# Sheet4.net
KiCad netlist of a schematic drawn in Altium Designer
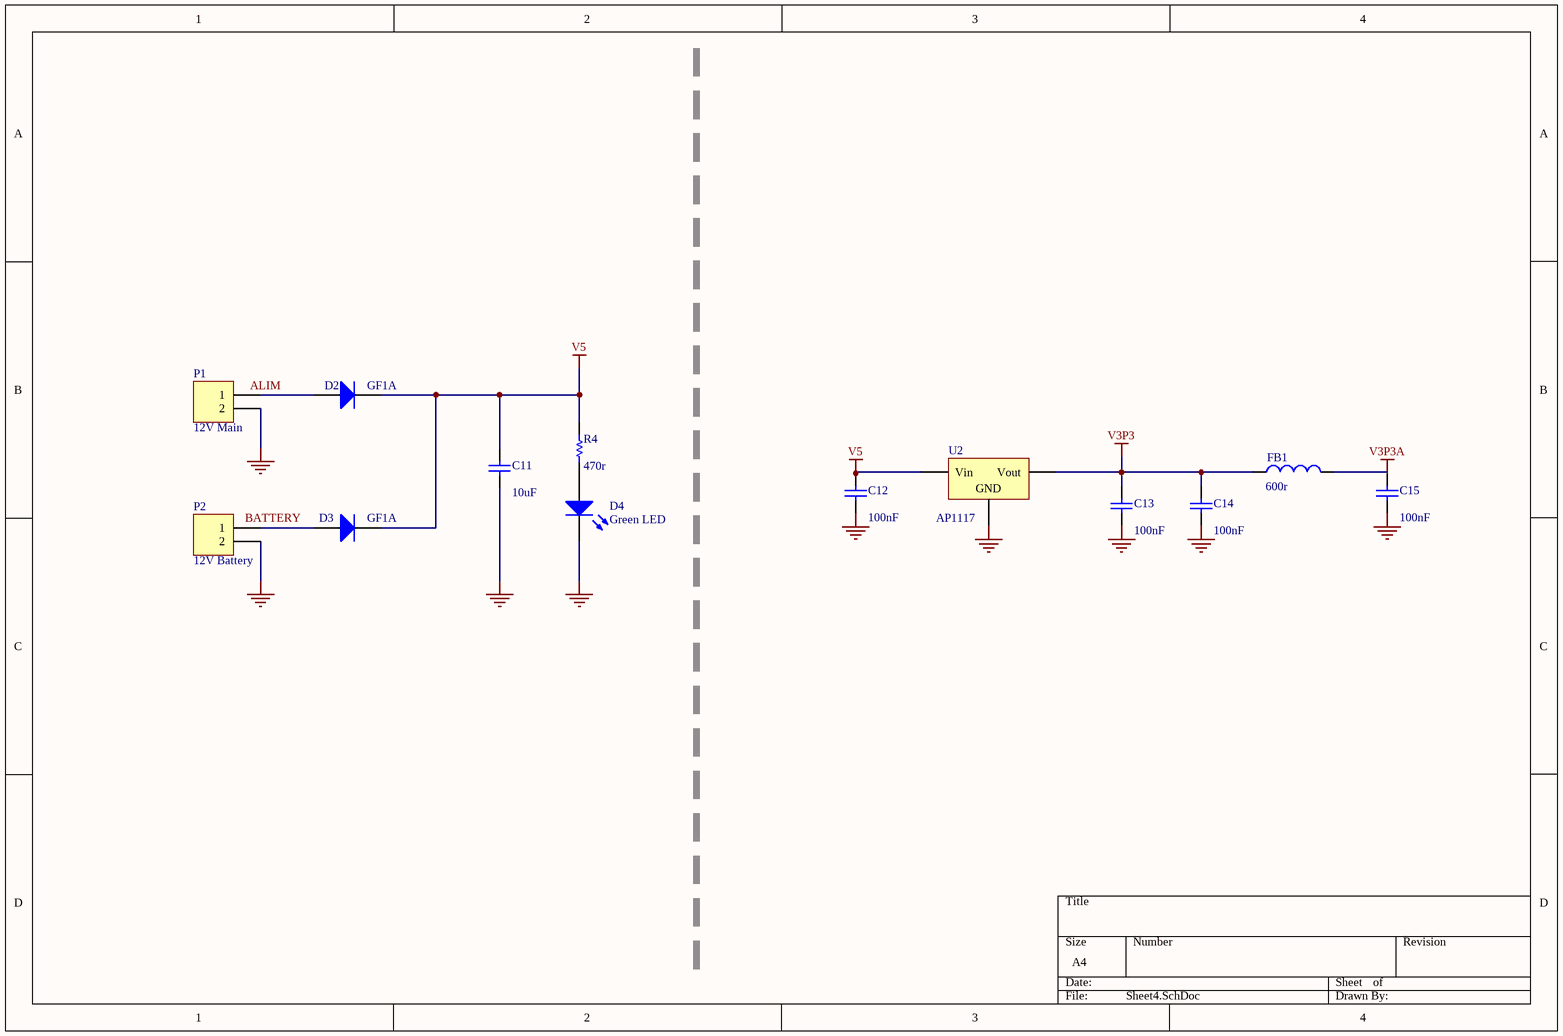
[diagram p0: Sheet4.SchDoc]

(export (version "E")
  (design (tool "Eeschema 10.0.6"))
  (components
    (comp (ref "C11")
      (value "10uF")
      (footprint "RAD-0.3")
      (description "Capacitor")
      (fields (field (name "Comment") "Cap") (field (name "PUBLISHER") "Altium Limited"))
      (libsource (lib "Miscellaneous Devices") (part "Cap"))
    )
    (comp (ref "C12")
      (value "100nF")
      (footprint "RAD-0.3")
      (description "Capacitor")
      (fields (field (name "Comment") "Cap") (field (name "PUBLISHER") "Altium Limited"))
      (libsource (lib "Miscellaneous Devices") (part "Cap"))
    )
    (comp (ref "C13")
      (value "100nF")
      (footprint "RAD-0.3")
      (description "Capacitor")
      (fields (field (name "Comment") "Cap") (field (name "PUBLISHER") "Altium Limited"))
      (libsource (lib "Miscellaneous Devices") (part "Cap"))
    )
    (comp (ref "C14")
      (value "100nF")
      (footprint "RAD-0.3")
      (description "Capacitor")
      (fields (field (name "Comment") "Cap") (field (name "PUBLISHER") "Altium Limited"))
      (libsource (lib "Miscellaneous Devices") (part "Cap"))
    )
    (comp (ref "C15")
      (value "100nF")
      (footprint "RAD-0.3")
      (description "Capacitor")
      (fields (field (name "Comment") "Cap") (field (name "PUBLISHER") "Altium Limited"))
      (libsource (lib "Miscellaneous Devices") (part "Cap"))
    )
    (comp (ref "D2")
      (value "GF1A")
      (footprint "SMC")
      (description "Default Diode")
      (fields (field (name "PUBLISHER") "Altium Limited"))
      (libsource (lib "Miscellaneous Devices") (part "Diode"))
    )
    (comp (ref "D3")
      (value "GF1A")
      (footprint "SMC")
      (description "Default Diode")
      (fields (field (name "PUBLISHER") "Altium Limited"))
      (libsource (lib "Miscellaneous Devices") (part "Diode"))
    )
    (comp (ref "D4")
      (value "Green LED")
      (footprint "3.2X1.6X1.1")
      (description "Typical RED, GREEN, YELLOW, AMBER GaAs LED")
      (fields (field (name "PUBLISHER") "Altium Limited"))
      (libsource (lib "Miscellaneous Devices") (part "LED2"))
    )
    (comp (ref "FB1")
      (value "600r")
      (footprint "0402-A")
      (description "Inductor")
      (fields (field (name "PUBLISHER") "Altium Limited"))
      (libsource (lib "Miscellaneous Devices") (part "Inductor"))
    )
    (comp (ref "P1")
      (value "12V Main")
      (footprint "HDR1X2")
      (description "Header, 2-Pin")
      (libsource (lib "Miscellaneous Connectors") (part "Header 2"))
    )
    (comp (ref "P2")
      (value "12V Battery")
      (footprint "HDR1X2")
      (description "Header, 2-Pin")
      (libsource (lib "Miscellaneous Connectors") (part "Header 2"))
    )
    (comp (ref "R4")
      (value "470r")
      (footprint "AXIAL-0.3")
      (description "Resistor")
      (fields (field (name "Comment") "Res1") (field (name "PUBLISHER") "Altium Limited"))
      (libsource (lib "Miscellaneous Devices") (part "Res1"))
    )
    (comp (ref "U2")
      (value "AP1117")
      (footprint "D2PAK_N")
      (description "Voltage Regulator")
      (fields (field (name "PUBLISHER") "Altium Limited"))
      (libsource (lib "Miscellaneous Devices") (part "Volt Reg"))
    )
  )
  (nets
    (net (code "3") (name "<NO NET>") (class "Default")
      (node (ref "C12") (pin "1") (pinfunction "1_1") (pintype "passive"))
      (node (ref "C13") (pin "1") (pinfunction "1_1") (pintype "passive"))
      (node (ref "C14") (pin "1") (pinfunction "1_1") (pintype "passive"))
      (node (ref "C15") (pin "1") (pinfunction "1_1") (pintype "passive"))
    )
    (net (code "4") (name "GND") (class "Default")
      (node (ref "C11") (pin "1") (pinfunction "1_1") (pintype "passive"))
      (node (ref "D4") (pin "2") (pinfunction "K_2") (pintype "passive"))
      (node (ref "P1") (pin "2") (pinfunction "2_2") (pintype "passive"))
      (node (ref "P2") (pin "2") (pinfunction "2_2") (pintype "passive"))
      (node (ref "U2") (pin "2") (pinfunction "GND_2") (pintype "passive"))
    )
    (net (code "5") (name "Net-(D2-A)") (class "Default")
      (node (ref "D2") (pin "1") (pinfunction "A_1") (pintype "passive"))
      (node (ref "P1") (pin "1") (pinfunction "1_1") (pintype "passive"))
    )
    (net (code "6") (name "Net-(D3-A)") (class "Default")
      (node (ref "D3") (pin "1") (pinfunction "A_1") (pintype "passive"))
      (node (ref "P2") (pin "1") (pinfunction "1_1") (pintype "passive"))
    )
    (net (code "7") (name "V3P3") (class "Default")
      (node (ref "C13") (pin "2") (pinfunction "2_2") (pintype "passive"))
      (node (ref "C14") (pin "2") (pinfunction "2_2") (pintype "passive"))
      (node (ref "FB1") (pin "1") (pinfunction "1_1") (pintype "passive"))
      (node (ref "U2") (pin "3") (pinfunction "Vout_3") (pintype "passive"))
    )
    (net (code "8") (name "V3P3A") (class "Default")
      (node (ref "C15") (pin "2") (pinfunction "2_2") (pintype "passive"))
    )
    (net (code "9") (name "V5") (class "Default")
      (node (ref "C11") (pin "2") (pinfunction "2_2") (pintype "passive"))
      (node (ref "C12") (pin "2") (pinfunction "2_2") (pintype "passive"))
      (node (ref "D2") (pin "2") (pinfunction "K_2") (pintype "passive"))
      (node (ref "D3") (pin "2") (pinfunction "K_2") (pintype "passive"))
      (node (ref "R4") (pin "1") (pinfunction "1_1") (pintype "passive"))
      (node (ref "U2") (pin "1") (pinfunction "Vin_1") (pintype "passive"))
    )
    (net (code "10") (name "unconnected-(D4-A-Pad1)") (class "Default")
      (node (ref "D4") (pin "1") (pinfunction "A_1") (pintype "passive"))
    )
    (net (code "11") (name "unconnected-(FB1-Pad2)") (class "Default")
      (node (ref "FB1") (pin "2") (pinfunction "2_2") (pintype "passive"))
    )
    (net (code "12") (name "unconnected-(R4-Pad2)") (class "Default")
      (node (ref "R4") (pin "2") (pinfunction "2_2") (pintype "passive"))
    )
  )
)
